# flash.net
KiCad netlist of a schematic drawn in Altium Designer
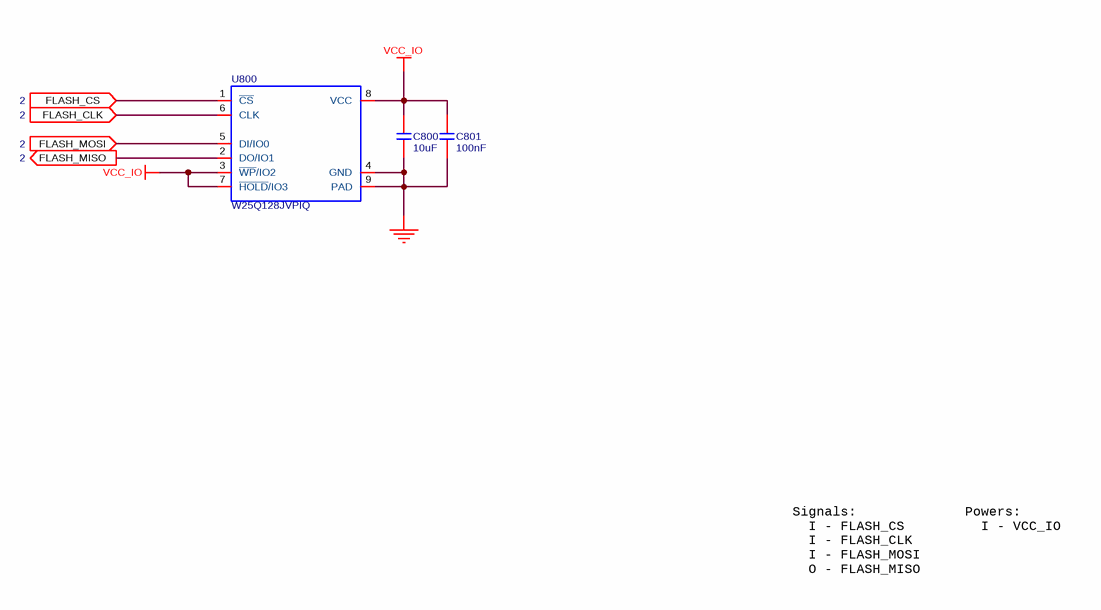
[diagram p0: flash.schdoc]

(export (version "E")
  (design (tool "Eeschema 10.0.6"))
  (components
    (comp (ref "C800")
      (value "10uF")
      (footprint "mw:C0402")
      (fields (field (name "VOLTAGE") "6.3V") (field (name "Comment") "C-NOMO"))
      (libsource (lib "mw") (part "C-NOMO"))
    )
    (comp (ref "C801")
      (value "100nF")
      (footprint "mw:C0402")
      (fields (field (name "VOLTAGE") "50V") (field (name "Comment") "C-NOMO"))
      (libsource (lib "mw") (part "C-NOMO"))
    )
    (comp (ref "U800")
      (value "W25Q128JVPIQ")
      (footprint "mw:W25Q128JVPIQ")
      (description "NOR FLASH")
      (libsource (lib "mw") (part "W25Q128JVPIQ"))
    )
  )
  (nets
    (net (code "1") (name "/FLASH_CLK") (class "Default")
      (node (ref "U800") (pin "6") (pinfunction "CLK_6") (pintype "passive"))
    )
    (net (code "2") (name "/FLASH_CS") (class "Default")
      (node (ref "U800") (pin "1") (pinfunction "~{CS}_1") (pintype "passive"))
    )
    (net (code "3") (name "/FLASH_MISO") (class "Default")
      (node (ref "U800") (pin "2") (pinfunction "DO/IO1_2") (pintype "passive"))
    )
    (net (code "4") (name "/FLASH_MOSI") (class "Default")
      (node (ref "U800") (pin "5") (pinfunction "DI/IO0_5") (pintype "passive"))
    )
    (net (code "5") (name "GND") (class "Default")
      (node (ref "C800") (pin "2") (pinfunction "2_2") (pintype "passive"))
      (node (ref "C801") (pin "2") (pinfunction "2_2") (pintype "passive"))
      (node (ref "U800") (pin "4") (pinfunction "GND_4") (pintype "passive"))
      (node (ref "U800") (pin "9") (pinfunction "PAD_9") (pintype "passive"))
    )
    (net (code "6") (name "VCC_IO") (class "Default")
      (node (ref "C800") (pin "1") (pinfunction "1_1") (pintype "passive"))
      (node (ref "C801") (pin "1") (pinfunction "1_1") (pintype "passive"))
      (node (ref "U800") (pin "3") (pinfunction "~{WP}/IO2_3") (pintype "passive"))
      (node (ref "U800") (pin "7") (pinfunction "~{HOLD}/IO3_7") (pintype "passive"))
      (node (ref "U800") (pin "8") (pinfunction "VCC_8") (pintype "passive"))
    )
  )
)
